# 5_ButtonsAndLeds.net
KiCad netlist of a schematic drawn in Altium Designer
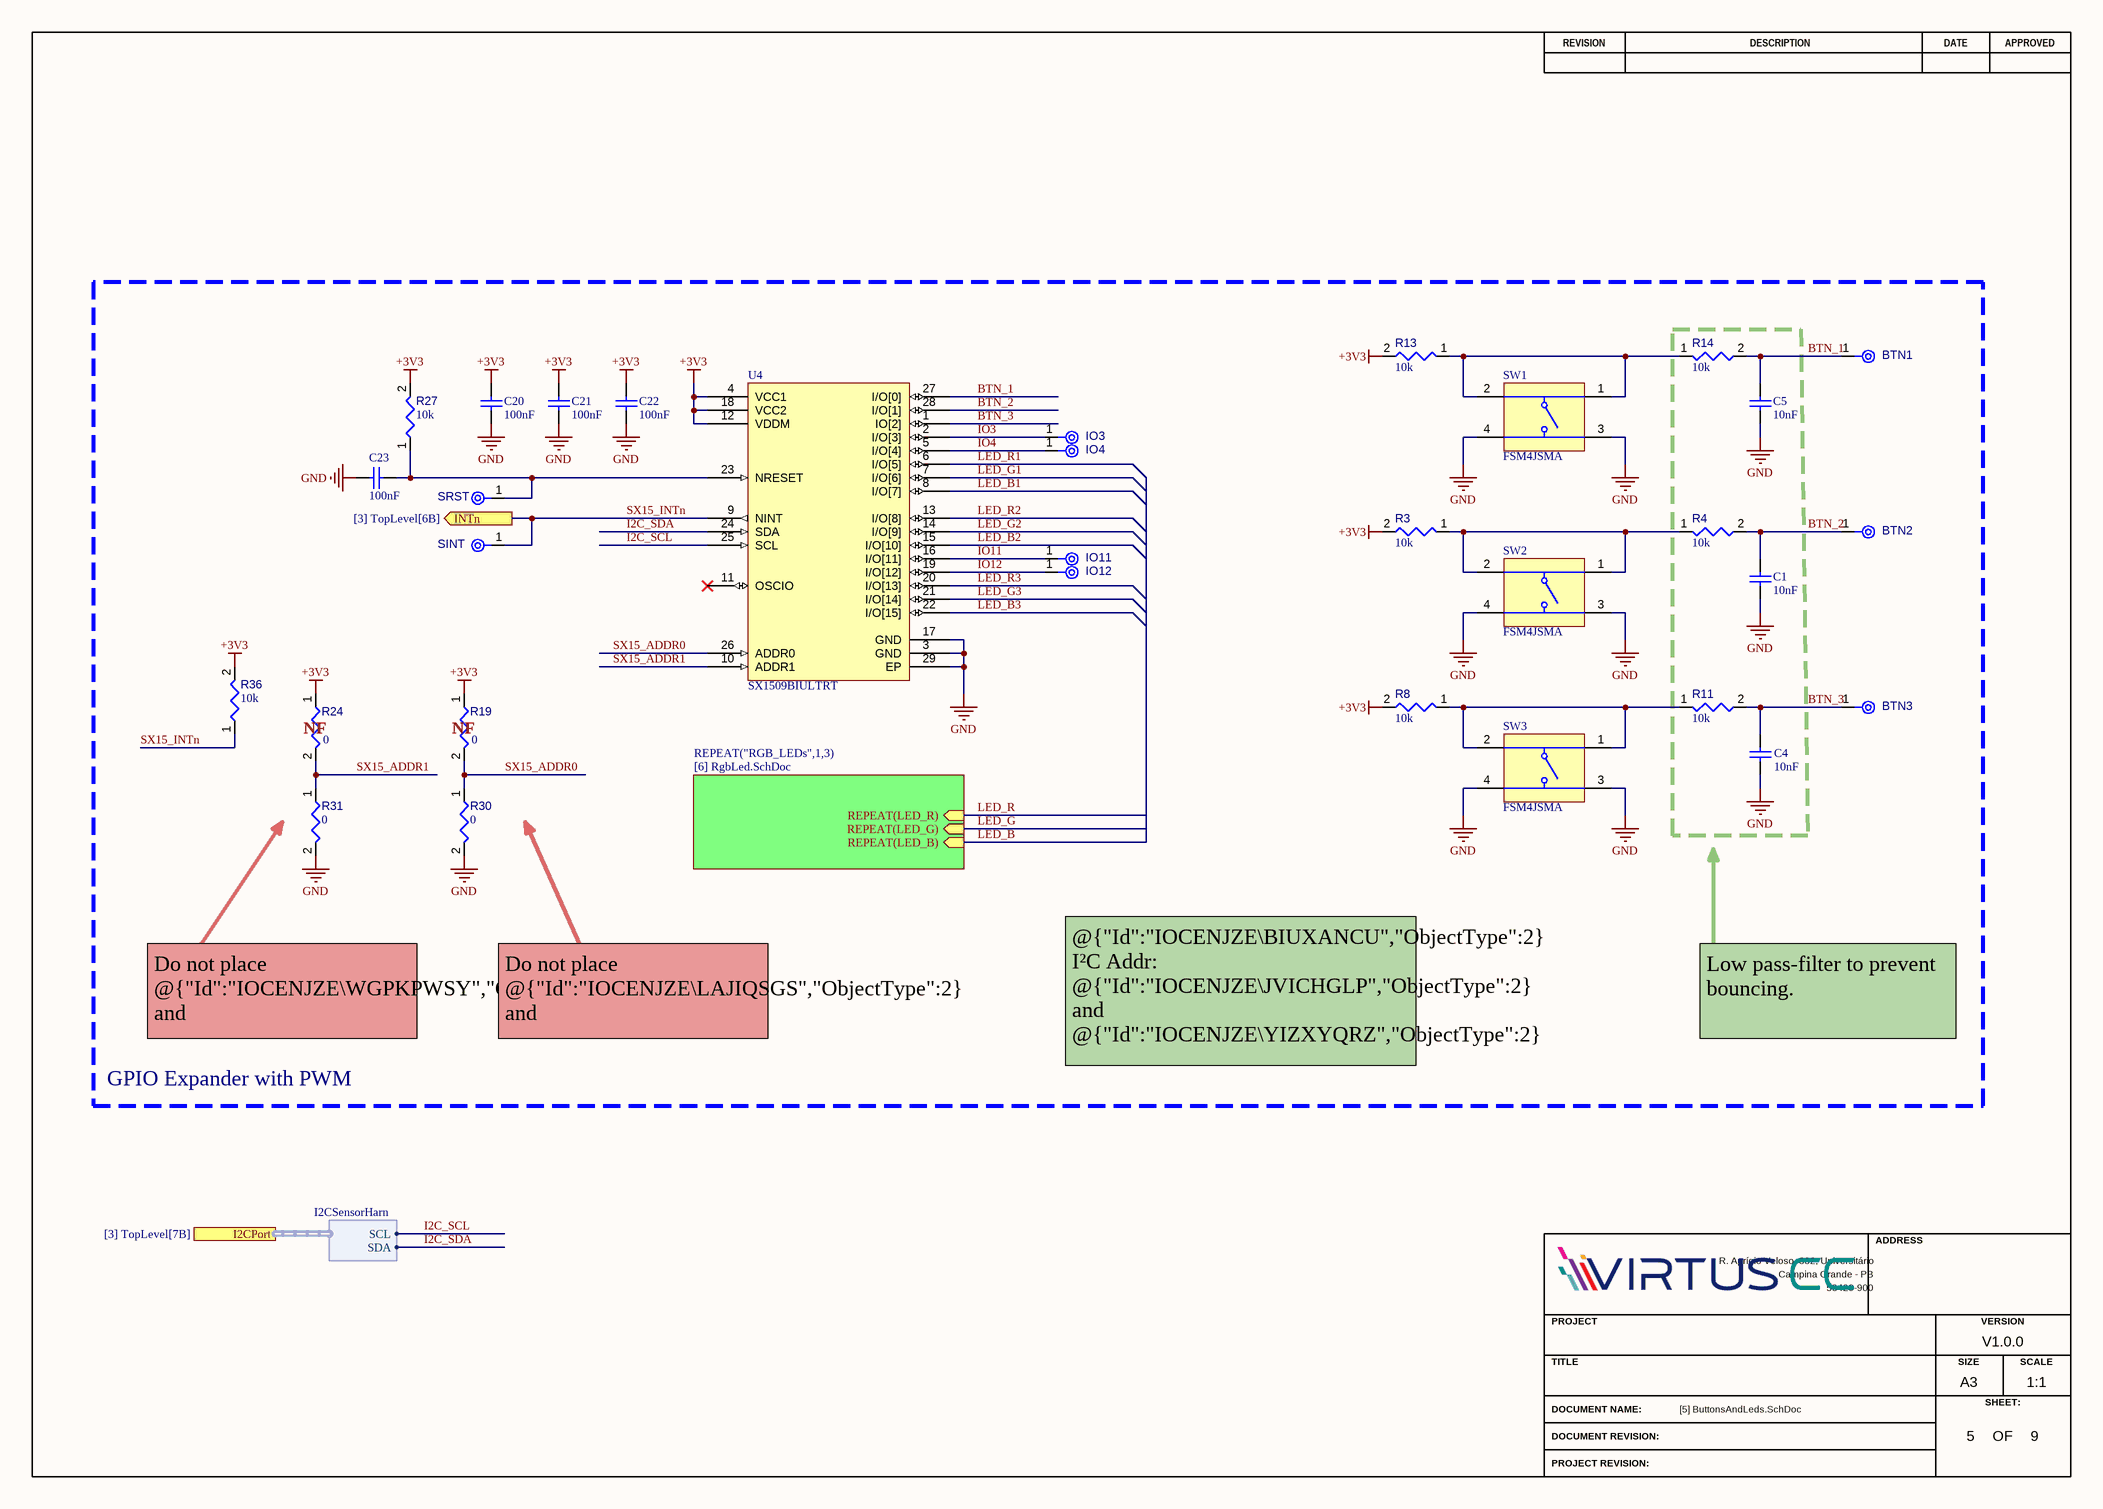
[diagram p0: [5] ButtonsAndLeds.SchDoc]

(export (version "E")
  (design (tool "Eeschema 10.0.6"))
  (components
    (comp (ref "BTN1")
      (value "TPAD6R")
      (footprint "TP06R")
      (description "0.6mm round")
      (libsource (lib "UFCG - Universidade Federal de Campina Grande") (part "CMP-001-0001-4"))
    )
    (comp (ref "BTN2")
      (value "TPAD6R")
      (footprint "TP06R")
      (description "0.6mm round")
      (libsource (lib "UFCG - Universidade Federal de Campina Grande") (part "CMP-001-0001-4"))
    )
    (comp (ref "BTN3")
      (value "TPAD6R")
      (footprint "TP06R")
      (description "0.6mm round")
      (libsource (lib "UFCG - Universidade Federal de Campina Grande") (part "CMP-001-0001-4"))
    )
    (comp (ref "C1")
      (value "10nF")
      (footprint "CAPC0603(1608)100_L")
      (description "Multilayer Ceramic Capacitor, 0.01 uF, 50 V, ± 10%, X7R, 0603 [1608 Metric]")
      (fields (field (name "VOLTAGE") "50V") (field (name "TOLERANCE") "10%"))
      (libsource (lib "UFCG - Universidade Federal de Campina Grande") (part "CAP"))
    )
    (comp (ref "C4")
      (value "10nF")
      (footprint "CAPC0603(1608)100_L")
      (description "Multilayer Ceramic Capacitor, 0.01 uF, 50 V, ± 10%, X7R, 0603 [1608 Metric]")
      (fields (field (name "VOLTAGE") "50V") (field (name "TOLERANCE") "10%"))
      (libsource (lib "UFCG - Universidade Federal de Campina Grande") (part "CAP"))
    )
    (comp (ref "C5")
      (value "10nF")
      (footprint "CAPC0603(1608)100_L")
      (description "Multilayer Ceramic Capacitor, 0.01 uF, 50 V, ± 10%, X7R, 0603 [1608 Metric]")
      (fields (field (name "VOLTAGE") "50V") (field (name "TOLERANCE") "10%"))
      (libsource (lib "UFCG - Universidade Federal de Campina Grande") (part "CAP"))
    )
    (comp (ref "C20")
      (value "100nF")
      (footprint "CAPC0603(1608)100_L")
      (description "Multilayer Ceramic Capacitor, 0.1 uF, 16 V, ± 20%, X7R, 0603 [1608 Metric]")
      (fields (field (name "TOLERANCE") "20%") (field (name "Comment") "VJ0603Y104MXJCW1BC"))
      (libsource (lib "UFCG - Universidade Federal de Campina Grande") (part "CAP"))
    )
    (comp (ref "C21")
      (value "100nF")
      (footprint "CAPC0603(1608)100_L")
      (description "Multilayer Ceramic Capacitor, 0.1 uF, 16 V, ± 20%, X7R, 0603 [1608 Metric]")
      (fields (field (name "TOLERANCE") "20%") (field (name "Comment") "VJ0603Y104MXJCW1BC"))
      (libsource (lib "UFCG - Universidade Federal de Campina Grande") (part "CAP"))
    )
    (comp (ref "C22")
      (value "100nF")
      (footprint "CAPC0603(1608)100_L")
      (description "Multilayer Ceramic Capacitor, 0.1 uF, 16 V, ± 20%, X7R, 0603 [1608 Metric]")
      (fields (field (name "TOLERANCE") "20%") (field (name "Comment") "VJ0603Y104MXJCW1BC"))
      (libsource (lib "UFCG - Universidade Federal de Campina Grande") (part "CAP"))
    )
    (comp (ref "C23")
      (value "100nF")
      (footprint "CAPC0603(1608)100_L")
      (description "Multilayer Ceramic Capacitor, 0.1 uF, 16 V, ± 20%, X7R, 0603 [1608 Metric]")
      (fields (field (name "TOLERANCE") "20%") (field (name "Comment") "VJ0603Y104MXJCW1BC"))
      (libsource (lib "UFCG - Universidade Federal de Campina Grande") (part "CAP"))
    )
    (comp (ref "IO3")
      (value "TPAD6R")
      (footprint "TP06R")
      (description "0.6mm round")
      (libsource (lib "UFCG - Universidade Federal de Campina Grande") (part "CMP-001-0001-4"))
    )
    (comp (ref "IO4")
      (value "TPAD6R")
      (footprint "TP06R")
      (description "0.6mm round")
      (libsource (lib "UFCG - Universidade Federal de Campina Grande") (part "CMP-001-0001-4"))
    )
    (comp (ref "IO11")
      (value "TPAD6R")
      (footprint "TP06R")
      (description "0.6mm round")
      (libsource (lib "UFCG - Universidade Federal de Campina Grande") (part "CMP-001-0001-4"))
    )
    (comp (ref "IO12")
      (value "TPAD6R")
      (footprint "TP06R")
      (description "0.6mm round")
      (libsource (lib "UFCG - Universidade Federal de Campina Grande") (part "CMP-001-0001-4"))
    )
    (comp (ref "R3")
      (value "10k")
      (footprint "RESC0603(1608)_L")
      (description "Chip Resistor, 10 KOhm, +/- 1%, 01 W, -55 to 155 degC, 0603 (1608 Metric)")
      (fields (field (name "POWER") "100mW") (field (name "TOLERANCE") "1%"))
      (libsource (lib "UFCG - Universidade Federal de Campina Grande") (part "RES-2"))
    )
    (comp (ref "R4")
      (value "10k")
      (footprint "RESC0603(1608)_L")
      (description "Chip Resistor, 10 KOhm, +/- 1%, 01 W, -55 to 155 degC, 0603 (1608 Metric)")
      (fields (field (name "POWER") "100mW") (field (name "TOLERANCE") "1%"))
      (libsource (lib "UFCG - Universidade Federal de Campina Grande") (part "RES-2"))
    )
    (comp (ref "R8")
      (value "10k")
      (footprint "RESC0603(1608)_L")
      (description "Chip Resistor, 10 KOhm, +/- 1%, 01 W, -55 to 155 degC, 0603 (1608 Metric)")
      (fields (field (name "POWER") "100mW") (field (name "TOLERANCE") "1%"))
      (libsource (lib "UFCG - Universidade Federal de Campina Grande") (part "RES-2"))
    )
    (comp (ref "R11")
      (value "10k")
      (footprint "RESC0603(1608)_L")
      (description "Chip Resistor, 10 KOhm, +/- 1%, 01 W, -55 to 155 degC, 0603 (1608 Metric)")
      (fields (field (name "POWER") "100mW") (field (name "TOLERANCE") "1%"))
      (libsource (lib "UFCG - Universidade Federal de Campina Grande") (part "RES-2"))
    )
    (comp (ref "R13")
      (value "10k")
      (footprint "RESC0603(1608)_L")
      (description "Chip Resistor, 10 KOhm, +/- 1%, 01 W, -55 to 155 degC, 0603 (1608 Metric)")
      (fields (field (name "POWER") "100mW") (field (name "TOLERANCE") "1%"))
      (libsource (lib "UFCG - Universidade Federal de Campina Grande") (part "RES-2"))
    )
    (comp (ref "R14")
      (value "10k")
      (footprint "RESC0603(1608)_L")
      (description "Chip Resistor, 10 KOhm, +/- 1%, 01 W, -55 to 155 degC, 0603 (1608 Metric)")
      (fields (field (name "POWER") "100mW") (field (name "TOLERANCE") "1%"))
      (libsource (lib "UFCG - Universidade Federal de Campina Grande") (part "RES-2"))
    )
    (comp (ref "R19")
      (value "0")
      (footprint "RESC0603(1608)_L")
      (description "Chip Resistor, 0 Ohm, 0.1 W, -55 to 155 degC, 0603 (1608 Metric)")
      (fields (field (name "TOLERANCE") "5%") (field (name "POWER") "100mW"))
      (libsource (lib "UFCG - Universidade Federal de Campina Grande") (part "RES-2"))
    )
    (comp (ref "R24")
      (value "0")
      (footprint "RESC0603(1608)_L")
      (description "Chip Resistor, 0 Ohm, 0.1 W, -55 to 155 degC, 0603 (1608 Metric)")
      (fields (field (name "TOLERANCE") "5%") (field (name "POWER") "100mW"))
      (libsource (lib "UFCG - Universidade Federal de Campina Grande") (part "RES-2"))
    )
    (comp (ref "R27")
      (value "10k")
      (footprint "RESC0603(1608)_L")
      (description "Chip Resistor, 10 KOhm, +/- 1%, 01 W, -55 to 155 degC, 0603 (1608 Metric)")
      (fields (field (name "POWER") "100mW") (field (name "TOLERANCE") "1%"))
      (libsource (lib "UFCG - Universidade Federal de Campina Grande") (part "RES-2"))
    )
    (comp (ref "R30")
      (value "0")
      (footprint "RESC0603(1608)_L")
      (description "Chip Resistor, 0 Ohm, 0.1 W, -55 to 155 degC, 0603 (1608 Metric)")
      (fields (field (name "TOLERANCE") "5%") (field (name "POWER") "100mW"))
      (libsource (lib "UFCG - Universidade Federal de Campina Grande") (part "RES-2"))
    )
    (comp (ref "R31")
      (value "0")
      (footprint "RESC0603(1608)_L")
      (description "Chip Resistor, 0 Ohm, 0.1 W, -55 to 155 degC, 0603 (1608 Metric)")
      (fields (field (name "TOLERANCE") "5%") (field (name "POWER") "100mW"))
      (libsource (lib "UFCG - Universidade Federal de Campina Grande") (part "RES-2"))
    )
    (comp (ref "R36")
      (value "10k")
      (footprint "RESC0603(1608)_L")
      (description "Chip Resistor, 10 KOhm, +/- 1%, 01 W, -55 to 155 degC, 0603 (1608 Metric)")
      (fields (field (name "POWER") "100mW") (field (name "TOLERANCE") "1%"))
      (libsource (lib "UFCG - Universidade Federal de Campina Grande") (part "RES-2"))
    )
    (comp (ref "SINT")
      (value "TPAD6R")
      (footprint "TP06R")
      (description "0.6mm round")
      (libsource (lib "UFCG - Universidade Federal de Campina Grande") (part "CMP-001-0001-4"))
    )
    (comp (ref "SRST")
      (value "TPAD6R")
      (footprint "TP06R")
      (description "0.6mm round")
      (libsource (lib "UFCG - Universidade Federal de Campina Grande") (part "CMP-001-0001-4"))
    )
    (comp (ref "SW1")
      (value "FSM4JSMA")
      (footprint "TECO-FSM4JSMA_V")
      (description "Switch Tactile OFF (ON) SPST Round Button Gull Wing 0.05A 12VDC 1.57N SMD Loose Piece")
      (libsource (lib "UFCG - Universidade Federal de Campina Grande") (part "SW-SPST-4_A"))
    )
    (comp (ref "SW2")
      (value "FSM4JSMA")
      (footprint "TECO-FSM4JSMA_V")
      (description "Switch Tactile OFF (ON) SPST Round Button Gull Wing 0.05A 12VDC 1.57N SMD Loose Piece")
      (libsource (lib "UFCG - Universidade Federal de Campina Grande") (part "SW-SPST-4_A"))
    )
    (comp (ref "SW3")
      (value "FSM4JSMA")
      (footprint "TECO-FSM4JSMA_V")
      (description "Switch Tactile OFF (ON) SPST Round Button Gull Wing 0.05A 12VDC 1.57N SMD Loose Piece")
      (libsource (lib "UFCG - Universidade Federal de Campina Grande") (part "SW-SPST-4_A"))
    )
    (comp (ref "U4")
      (value "SX1509BIULTRT")
      (footprint "QFN40P410X410X60_HS-29N")
      (description "IC Gpio Expander I2C 16CH 28QFN / I2C Interface 5.5V 28-PIN Qfn-ut Ep T/r")
      (libsource (lib "UFCG - Universidade Federal de Campina Grande") (part "New symbol 1"))
    )
  )
  (nets
    (net (code "2") (name "+3V3") (class "Default")
      (node (ref "C20") (pin "1") (pinfunction "1_1") (pintype "passive"))
      (node (ref "C21") (pin "1") (pinfunction "1_1") (pintype "passive"))
      (node (ref "C22") (pin "1") (pinfunction "1_1") (pintype "passive"))
      (node (ref "R13") (pin "2") (pinfunction "2_2") (pintype "passive"))
      (node (ref "R19") (pin "1") (pinfunction "1_1") (pintype "passive"))
      (node (ref "R24") (pin "1") (pinfunction "1_1") (pintype "passive"))
      (node (ref "R27") (pin "2") (pinfunction "2_2") (pintype "passive"))
      (node (ref "R3") (pin "2") (pinfunction "2_2") (pintype "passive"))
      (node (ref "R36") (pin "2") (pinfunction "2_2") (pintype "passive"))
      (node (ref "R8") (pin "2") (pinfunction "2_2") (pintype "passive"))
      (node (ref "U4") (pin "12") (pinfunction "VDDM_12") (pintype "power_in"))
      (node (ref "U4") (pin "18") (pinfunction "VCC2_18") (pintype "power_in"))
      (node (ref "U4") (pin "4") (pinfunction "VCC1_4") (pintype "power_in"))
    )
    (net (code "3") (name "/BTN_1") (class "Default")
      (node (ref "BTN1") (pin "1") (pinfunction "TP_1") (pintype "passive"))
      (node (ref "C5") (pin "2") (pinfunction "2_2") (pintype "passive"))
      (node (ref "R14") (pin "2") (pinfunction "2_2") (pintype "passive"))
      (node (ref "U4") (pin "27") (pinfunction "I/O[0]_27") (pintype "bidirectional"))
    )
    (net (code "4") (name "/BTN_2") (class "Default")
      (node (ref "BTN2") (pin "1") (pinfunction "TP_1") (pintype "passive"))
      (node (ref "C1") (pin "2") (pinfunction "2_2") (pintype "passive"))
      (node (ref "R4") (pin "2") (pinfunction "2_2") (pintype "passive"))
      (node (ref "U4") (pin "28") (pinfunction "I/O[1]_28") (pintype "bidirectional"))
    )
    (net (code "5") (name "/BTN_3") (class "Default")
      (node (ref "BTN3") (pin "1") (pinfunction "TP_1") (pintype "passive"))
      (node (ref "C4") (pin "2") (pinfunction "2_2") (pintype "passive"))
      (node (ref "R11") (pin "2") (pinfunction "2_2") (pintype "passive"))
      (node (ref "U4") (pin "1") (pinfunction "IO[2]_1") (pintype "bidirectional"))
    )
    (net (code "6") (name "/I2C_SCL") (class "Default")
      (node (ref "U4") (pin "25") (pinfunction "SCL_25") (pintype "input"))
    )
    (net (code "7") (name "/I2C_SDA") (class "Default")
      (node (ref "U4") (pin "24") (pinfunction "SDA_24") (pintype "input"))
    )
    (net (code "8") (name "/IO3") (class "Default")
      (node (ref "IO3") (pin "1") (pinfunction "TP_1") (pintype "passive"))
      (node (ref "U4") (pin "2") (pinfunction "I/O[3]_2") (pintype "bidirectional"))
    )
    (net (code "9") (name "/IO4") (class "Default")
      (node (ref "IO4") (pin "1") (pinfunction "TP_1") (pintype "passive"))
      (node (ref "U4") (pin "5") (pinfunction "I/O[4]_5") (pintype "bidirectional"))
    )
    (net (code "10") (name "/IO11") (class "Default")
      (node (ref "IO11") (pin "1") (pinfunction "TP_1") (pintype "passive"))
      (node (ref "U4") (pin "16") (pinfunction "I/O[11]_16") (pintype "bidirectional"))
    )
    (net (code "11") (name "/IO12") (class "Default")
      (node (ref "IO12") (pin "1") (pinfunction "TP_1") (pintype "passive"))
      (node (ref "U4") (pin "19") (pinfunction "I/O[12]_19") (pintype "bidirectional"))
    )
    (net (code "13") (name "/LED_B1") (class "Default")
      (node (ref "U4") (pin "8") (pinfunction "I/O[7]_8") (pintype "bidirectional"))
    )
    (net (code "14") (name "/LED_B2") (class "Default")
      (node (ref "U4") (pin "15") (pinfunction "I/O[10]_15") (pintype "bidirectional"))
    )
    (net (code "15") (name "/LED_B3") (class "Default")
      (node (ref "U4") (pin "22") (pinfunction "I/O[15]_22") (pintype "bidirectional"))
    )
    (net (code "17") (name "/LED_G1") (class "Default")
      (node (ref "U4") (pin "7") (pinfunction "I/O[6]_7") (pintype "bidirectional"))
    )
    (net (code "18") (name "/LED_G2") (class "Default")
      (node (ref "U4") (pin "14") (pinfunction "I/O[9]_14") (pintype "bidirectional"))
    )
    (net (code "19") (name "/LED_G3") (class "Default")
      (node (ref "U4") (pin "21") (pinfunction "I/O[14]_21") (pintype "bidirectional"))
    )
    (net (code "21") (name "/LED_R1") (class "Default")
      (node (ref "U4") (pin "6") (pinfunction "I/O[5]_6") (pintype "bidirectional"))
    )
    (net (code "22") (name "/LED_R2") (class "Default")
      (node (ref "U4") (pin "13") (pinfunction "I/O[8]_13") (pintype "bidirectional"))
    )
    (net (code "23") (name "/LED_R3") (class "Default")
      (node (ref "U4") (pin "20") (pinfunction "I/O[13]_20") (pintype "bidirectional"))
    )
    (net (code "24") (name "/SX15_ADDR0") (class "Default")
      (node (ref "R19") (pin "2") (pinfunction "2_2") (pintype "passive"))
      (node (ref "R30") (pin "1") (pinfunction "1_1") (pintype "passive"))
      (node (ref "U4") (pin "26") (pinfunction "ADDR0_26") (pintype "input"))
    )
    (net (code "25") (name "/SX15_ADDR1") (class "Default")
      (node (ref "R24") (pin "2") (pinfunction "2_2") (pintype "passive"))
      (node (ref "R31") (pin "1") (pinfunction "1_1") (pintype "passive"))
      (node (ref "U4") (pin "10") (pinfunction "ADDR1_10") (pintype "input"))
    )
    (net (code "26") (name "/SX15_INTn") (class "Default")
      (node (ref "R36") (pin "1") (pinfunction "1_1") (pintype "passive"))
      (node (ref "SINT") (pin "1") (pinfunction "TP_1") (pintype "passive"))
      (node (ref "U4") (pin "9") (pinfunction "NINT_9") (pintype "output"))
    )
    (net (code "28") (name "GND") (class "Default")
      (node (ref "C1") (pin "1") (pinfunction "1_1") (pintype "passive"))
      (node (ref "C20") (pin "2") (pinfunction "2_2") (pintype "passive"))
      (node (ref "C21") (pin "2") (pinfunction "2_2") (pintype "passive"))
      (node (ref "C22") (pin "2") (pinfunction "2_2") (pintype "passive"))
      (node (ref "C23") (pin "2") (pinfunction "2_2") (pintype "passive"))
      (node (ref "C4") (pin "1") (pinfunction "1_1") (pintype "passive"))
      (node (ref "C5") (pin "1") (pinfunction "1_1") (pintype "passive"))
      (node (ref "R30") (pin "2") (pinfunction "2_2") (pintype "passive"))
      (node (ref "R31") (pin "2") (pinfunction "2_2") (pintype "passive"))
      (node (ref "SW1") (pin "3") (pinfunction "3_3") (pintype "passive"))
      (node (ref "SW1") (pin "4") (pinfunction "4_4") (pintype "passive"))
      (node (ref "SW2") (pin "3") (pinfunction "3_3") (pintype "passive"))
      (node (ref "SW2") (pin "4") (pinfunction "4_4") (pintype "passive"))
      (node (ref "SW3") (pin "3") (pinfunction "3_3") (pintype "passive"))
      (node (ref "SW3") (pin "4") (pinfunction "4_4") (pintype "passive"))
      (node (ref "U4") (pin "17") (pinfunction "GND_17") (pintype "power_in"))
      (node (ref "U4") (pin "29") (pinfunction "EP_29") (pintype "power_in"))
      (node (ref "U4") (pin "3") (pinfunction "GND_3") (pintype "power_in"))
    )
    (net (code "29") (name "Net-(R3-Pad1)") (class "Default")
      (node (ref "R3") (pin "1") (pinfunction "1_1") (pintype "passive"))
      (node (ref "R4") (pin "1") (pinfunction "1_1") (pintype "passive"))
      (node (ref "SW2") (pin "1") (pinfunction "1_1") (pintype "passive"))
      (node (ref "SW2") (pin "2") (pinfunction "2_2") (pintype "passive"))
    )
    (net (code "30") (name "Net-(R11-Pad1)") (class "Default")
      (node (ref "R11") (pin "1") (pinfunction "1_1") (pintype "passive"))
      (node (ref "R8") (pin "1") (pinfunction "1_1") (pintype "passive"))
      (node (ref "SW3") (pin "1") (pinfunction "1_1") (pintype "passive"))
      (node (ref "SW3") (pin "2") (pinfunction "2_2") (pintype "passive"))
    )
    (net (code "31") (name "Net-(R13-Pad1)") (class "Default")
      (node (ref "R13") (pin "1") (pinfunction "1_1") (pintype "passive"))
      (node (ref "R14") (pin "1") (pinfunction "1_1") (pintype "passive"))
      (node (ref "SW1") (pin "1") (pinfunction "1_1") (pintype "passive"))
      (node (ref "SW1") (pin "2") (pinfunction "2_2") (pintype "passive"))
    )
    (net (code "32") (name "Net-(SRST-TP)") (class "Default")
      (node (ref "C23") (pin "1") (pinfunction "1_1") (pintype "passive"))
      (node (ref "R27") (pin "1") (pinfunction "1_1") (pintype "passive"))
      (node (ref "SRST") (pin "1") (pinfunction "TP_1") (pintype "passive"))
      (node (ref "U4") (pin "23") (pinfunction "NRESET_23") (pintype "input"))
    )
    (net (code "33") (name "unconnected-(U4-OSCIO-Pad11)") (class "Default")
      (node (ref "U4") (pin "11") (pinfunction "OSCIO_11") (pintype "bidirectional+no_connect"))
    )
  )
)
